# MAZ000162_-_Diagrama_el_ctrico.net
KiCad netlist of a schematic drawn in Altium Designer
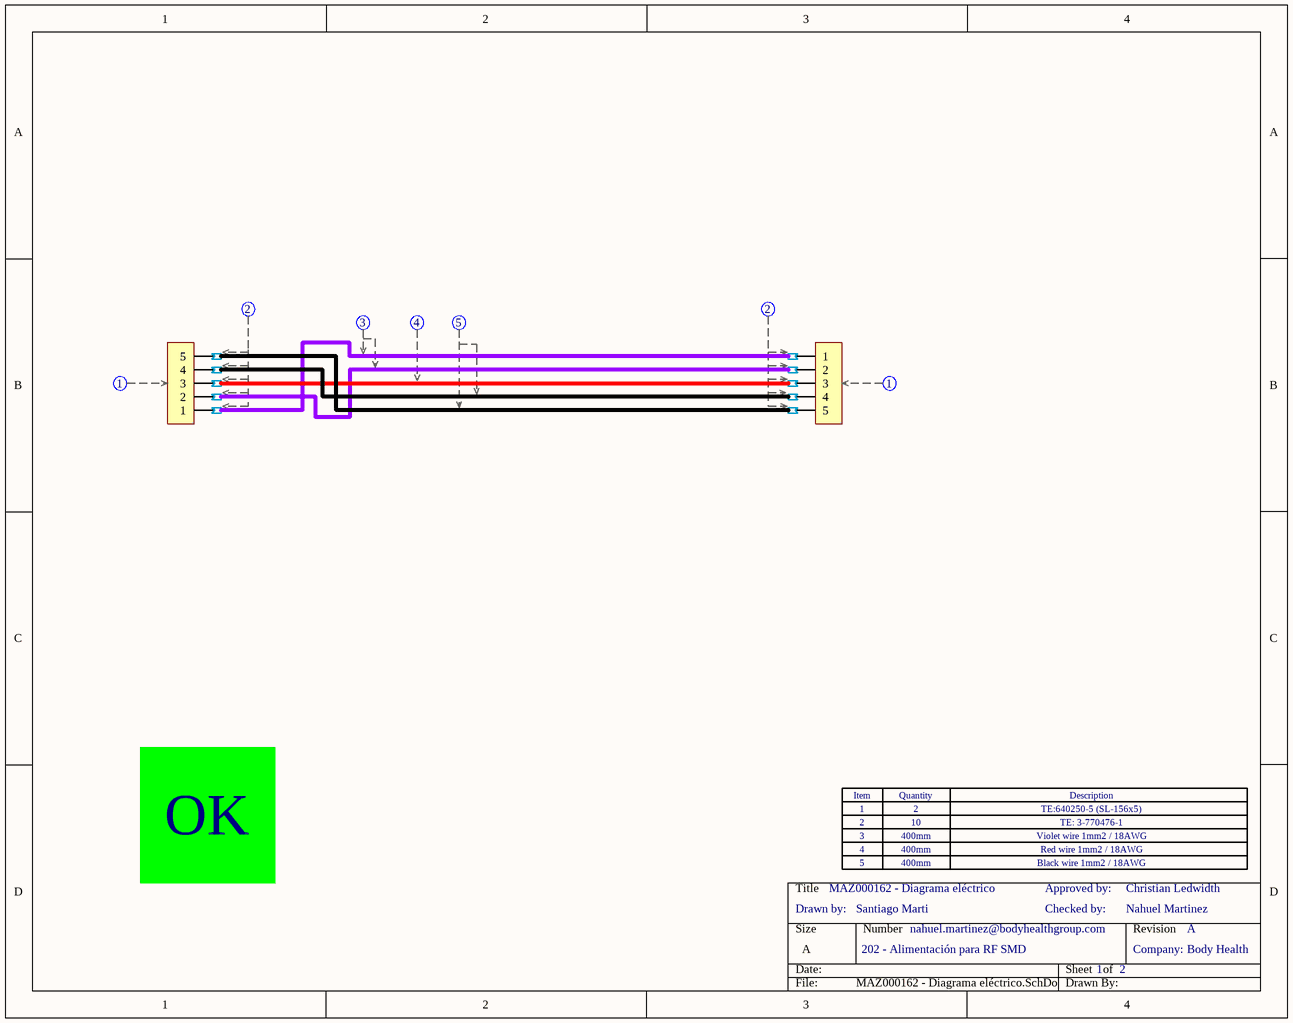
[diagram p0: MAZ000162 - Diagrama eléctrico.SchDoc]

(export (version "E")
  (design (tool "Eeschema 10.0.6"))
  (components
    (comp (ref "Con1")
      (value "SL156-5")
      (description "CONN RECEPT 5 POS W/RAMP SL-156")
      (libsource (lib "LibreriaParaPlanos") (part "SL156-5"))
    )
    (comp (ref "Con2")
      (value "SL156-5")
      (description "CONN RECEPT 5 POS W/RAMP SL-156")
      (libsource (lib "LibreriaParaPlanos") (part "SL156-5"))
    )
    (comp (ref "Soc1")
      (value "sock_SL156_770476-1")
      (description "CONN SOCKET 18-24AWG CRIMP TIN")
      (libsource (lib "LibreriaParaPlanos") (part "sock_SL156_770476-1"))
    )
    (comp (ref "Soc2")
      (value "sock_SL156_770476-1")
      (description "CONN SOCKET 18-24AWG CRIMP TIN")
      (libsource (lib "LibreriaParaPlanos") (part "sock_SL156_770476-1"))
    )
    (comp (ref "Soc3")
      (value "sock_SL156_770476-1")
      (description "CONN SOCKET 18-24AWG CRIMP TIN")
      (libsource (lib "LibreriaParaPlanos") (part "sock_SL156_770476-1"))
    )
    (comp (ref "Soc4")
      (value "sock_SL156_770476-1")
      (description "CONN SOCKET 18-24AWG CRIMP TIN")
      (libsource (lib "LibreriaParaPlanos") (part "sock_SL156_770476-1"))
    )
    (comp (ref "Soc5")
      (value "sock_SL156_770476-1")
      (description "CONN SOCKET 18-24AWG CRIMP TIN")
      (libsource (lib "LibreriaParaPlanos") (part "sock_SL156_770476-1"))
    )
    (comp (ref "Soc6")
      (value "sock_SL156_770476-1")
      (description "CONN SOCKET 18-24AWG CRIMP TIN")
      (libsource (lib "LibreriaParaPlanos") (part "sock_SL156_770476-1"))
    )
    (comp (ref "Soc7")
      (value "sock_SL156_770476-1")
      (description "CONN SOCKET 18-24AWG CRIMP TIN")
      (libsource (lib "LibreriaParaPlanos") (part "sock_SL156_770476-1"))
    )
    (comp (ref "Soc8")
      (value "sock_SL156_770476-1")
      (description "CONN SOCKET 18-24AWG CRIMP TIN")
      (libsource (lib "LibreriaParaPlanos") (part "sock_SL156_770476-1"))
    )
    (comp (ref "Soc9")
      (value "sock_SL156_770476-1")
      (description "CONN SOCKET 18-24AWG CRIMP TIN")
      (libsource (lib "LibreriaParaPlanos") (part "sock_SL156_770476-1"))
    )
    (comp (ref "Soc10")
      (value "sock_SL156_770476-1")
      (description "CONN SOCKET 18-24AWG CRIMP TIN")
      (libsource (lib "LibreriaParaPlanos") (part "sock_SL156_770476-1"))
    )
    (comp (ref "Zoc1")
      (value "Zócalo_Header")
      (description "Header para el zócalo de referencias")
      (libsource (lib "LibreriaParaPlanos") (part "Zócalo_Header"))
    )
    (comp (ref "Zoc2")
      (value "Zócalo_Item")
      (description "Ítem para el zócalo de referencias")
      (libsource (lib "LibreriaParaPlanos") (part "Zócalo_Item"))
    )
    (comp (ref "Zoc3")
      (value "Zócalo_Item")
      (description "Ítem para el zócalo de referencias")
      (libsource (lib "LibreriaParaPlanos") (part "Zócalo_Item"))
    )
    (comp (ref "Zoc4")
      (value "Zócalo_Item")
      (description "Ítem para el zócalo de referencias")
      (libsource (lib "LibreriaParaPlanos") (part "Zócalo_Item"))
    )
    (comp (ref "Zoc5")
      (value "Zócalo_Item")
      (description "Ítem para el zócalo de referencias")
      (libsource (lib "LibreriaParaPlanos") (part "Zócalo_Item"))
    )
    (comp (ref "Zoc6")
      (value "Zócalo_Item")
      (description "Ítem para el zócalo de referencias")
      (libsource (lib "LibreriaParaPlanos") (part "Zócalo_Item"))
    )
  )
  (nets
    (net (code "1") (name "Net-(Con1-Pad1)") (class "Default")
      (node (ref "Con1") (pin "1") (pinfunction "1_1") (pintype "passive"))
      (node (ref "Soc9") (pin "0") (pinfunction "0_0") (pintype "passive"))
    )
    (net (code "2") (name "Net-(Con1-Pad2)") (class "Default")
      (node (ref "Con1") (pin "2") (pinfunction "2_2") (pintype "passive"))
      (node (ref "Soc7") (pin "0") (pinfunction "0_0") (pintype "passive"))
    )
    (net (code "3") (name "Net-(Con1-Pad3)") (class "Default")
      (node (ref "Con1") (pin "3") (pinfunction "3_3") (pintype "passive"))
      (node (ref "Soc5") (pin "0") (pinfunction "0_0") (pintype "passive"))
    )
    (net (code "4") (name "Net-(Con1-Pad4)") (class "Default")
      (node (ref "Con1") (pin "4") (pinfunction "4_4") (pintype "passive"))
      (node (ref "Soc3") (pin "0") (pinfunction "0_0") (pintype "passive"))
    )
    (net (code "5") (name "Net-(Con1-Pad5)") (class "Default")
      (node (ref "Con1") (pin "5") (pinfunction "5_5") (pintype "passive"))
      (node (ref "Soc1") (pin "0") (pinfunction "0_0") (pintype "passive"))
    )
    (net (code "6") (name "Net-(Con2-Pad1)") (class "Default")
      (node (ref "Con2") (pin "1") (pinfunction "1_1") (pintype "passive"))
      (node (ref "Soc2") (pin "0") (pinfunction "0_0") (pintype "passive"))
    )
    (net (code "7") (name "Net-(Con2-Pad2)") (class "Default")
      (node (ref "Con2") (pin "2") (pinfunction "2_2") (pintype "passive"))
      (node (ref "Soc4") (pin "0") (pinfunction "0_0") (pintype "passive"))
    )
    (net (code "8") (name "Net-(Con2-Pad3)") (class "Default")
      (node (ref "Con2") (pin "3") (pinfunction "3_3") (pintype "passive"))
      (node (ref "Soc6") (pin "0") (pinfunction "0_0") (pintype "passive"))
    )
    (net (code "9") (name "Net-(Con2-Pad4)") (class "Default")
      (node (ref "Con2") (pin "4") (pinfunction "4_4") (pintype "passive"))
      (node (ref "Soc8") (pin "0") (pinfunction "0_0") (pintype "passive"))
    )
    (net (code "10") (name "Net-(Con2-Pad5)") (class "Default")
      (node (ref "Con2") (pin "5") (pinfunction "5_5") (pintype "passive"))
      (node (ref "Soc10") (pin "0") (pinfunction "0_0") (pintype "passive"))
    )
    (net (code "11") (name "Net-(Soc1-Pad1)") (class "Default")
      (node (ref "Soc1") (pin "1") (pinfunction "1_1") (pintype "passive"))
      (node (ref "Soc10") (pin "1") (pinfunction "1_1") (pintype "passive"))
    )
    (net (code "12") (name "Net-(Soc2-Pad1)") (class "Default")
      (node (ref "Soc2") (pin "1") (pinfunction "1_1") (pintype "passive"))
      (node (ref "Soc9") (pin "1") (pinfunction "1_1") (pintype "passive"))
    )
    (net (code "13") (name "Net-(Soc3-Pad1)") (class "Default")
      (node (ref "Soc3") (pin "1") (pinfunction "1_1") (pintype "passive"))
      (node (ref "Soc8") (pin "1") (pinfunction "1_1") (pintype "passive"))
    )
    (net (code "14") (name "Net-(Soc4-Pad1)") (class "Default")
      (node (ref "Soc4") (pin "1") (pinfunction "1_1") (pintype "passive"))
      (node (ref "Soc7") (pin "1") (pinfunction "1_1") (pintype "passive"))
    )
    (net (code "15") (name "Net-(Soc5-Pad1)") (class "Default")
      (node (ref "Soc5") (pin "1") (pinfunction "1_1") (pintype "passive"))
      (node (ref "Soc6") (pin "1") (pinfunction "1_1") (pintype "passive"))
    )
  )
)
